# attinier85-light-sensor-shield-mk-2_0.net
KiCad netlist of a schematic drawn in EAGLE
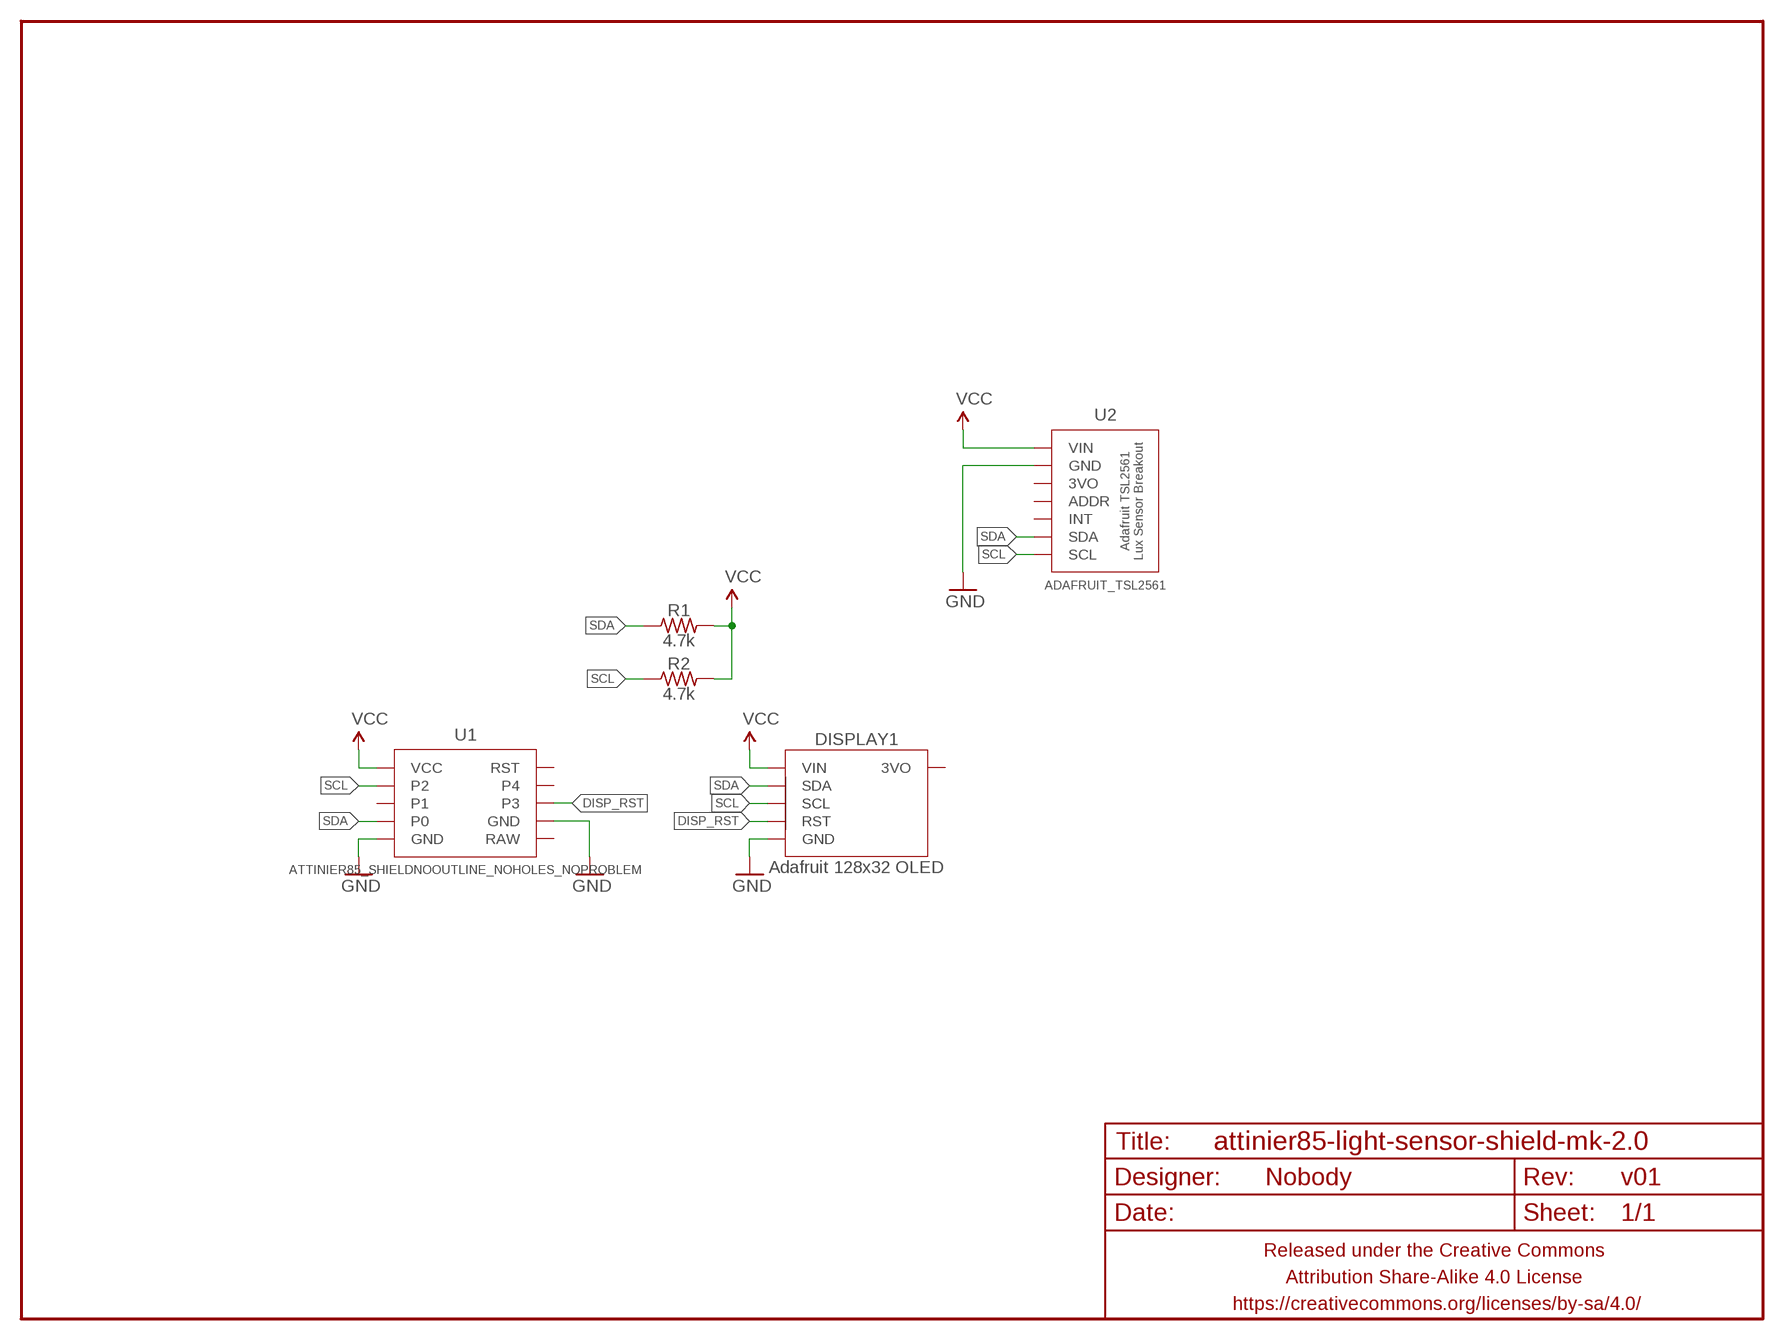
[diagram p0: schematic, sheet 1]

(export (version "E")
  (design (tool "Eeschema 10.0.6"))
  (components
    (comp (ref "DISPLAY1")
      (value "Adafruit 128x32 OLED")
      (footprint "eagle-import:ADAFRUIT_128X32_OLED_I2C_CLOSER_NOTITLE")
      (libsource (lib "eagle-import") (part "ADAFRUIT_128X32_OLED_I2CNOTITLE"))
    )
    (comp (ref "FRAME1")
      (value "FRAME-LETTERNO_PACKAGE")
      (footprint "eagle-import:DUMMY")
      (fields (field (name "DESIGNER") "Nobody"))
      (libsource (lib "eagle-import") (part "FRAME-LETTERNO_PACKAGE"))
    )
    (comp (ref "R1")
      (value "4.7k")
      (footprint "eagle-import:RESISTOR-AXIAL-PTH-7.62MM")
      (libsource (lib "eagle-import") (part "RESISTORPTH-AXIAL-7.62MM"))
    )
    (comp (ref "R2")
      (value "4.7k")
      (footprint "eagle-import:RESISTOR-AXIAL-PTH-7.62MM")
      (libsource (lib "eagle-import") (part "RESISTORPTH-AXIAL-7.62MM"))
    )
    (comp (ref "U1")
      (value "ATTINIER85_SHIELDNOOUTLINE_NOHOLES_NOPROBLEM")
      (footprint "eagle-import:ATTINIER_SHIELD_NOOUTLINE_NOHOLES")
      (libsource (lib "eagle-import") (part "ATTINIER85_SHIELDNOOUTLINE_NOHOLES_NOPROBLEM"))
    )
    (comp (ref "U2")
      (value "ADAFRUIT_TSL2561")
      (footprint "eagle-import:ADAFRUIT_TSL2561")
      (libsource (lib "eagle-import") (part "ADAFRUIT_TSL2561"))
    )
  )
  (nets
    (net (code "1") (name "DISP_RST") (class "Default")
      (node (ref "DISPLAY1") (pin "RST") (pinfunction "RST_RST") (pintype "bidirectional"))
      (node (ref "U1") (pin "3") (pinfunction "P3_3") (pintype "bidirectional"))
    )
    (net (code "2") (name "GND") (class "Default")
      (node (ref "DISPLAY1") (pin "GND") (pinfunction "GND_GND") (pintype "bidirectional"))
      (node (ref "U1") (pin "GND@1") (pinfunction "GND_GND@1") (pintype "bidirectional"))
      (node (ref "U1") (pin "GND@2") (pinfunction "GND_GND@2") (pintype "bidirectional"))
      (node (ref "U2") (pin "GND") (pinfunction "GND_GND") (pintype "bidirectional"))
    )
    (net (code "3") (name "SCL") (class "Default")
      (node (ref "DISPLAY1") (pin "SCL") (pinfunction "SCL_SCL") (pintype "bidirectional"))
      (node (ref "R2") (pin "P$1") (pinfunction "1_P$1") (pintype "passive"))
      (node (ref "U1") (pin "2") (pinfunction "P2_2") (pintype "bidirectional"))
      (node (ref "U2") (pin "SCL") (pinfunction "SCL_SCL") (pintype "bidirectional"))
    )
    (net (code "4") (name "SDA") (class "Default")
      (node (ref "DISPLAY1") (pin "SDA") (pinfunction "SDA_SDA") (pintype "bidirectional"))
      (node (ref "R1") (pin "P$1") (pinfunction "1_P$1") (pintype "passive"))
      (node (ref "U1") (pin "0") (pinfunction "P0_0") (pintype "bidirectional"))
      (node (ref "U2") (pin "SDA") (pinfunction "SDA_SDA") (pintype "bidirectional"))
    )
    (net (code "5") (name "VCC") (class "Default")
      (node (ref "DISPLAY1") (pin "VIN") (pinfunction "VIN_VIN") (pintype "bidirectional"))
      (node (ref "R1") (pin "P$2") (pinfunction "2_P$2") (pintype "passive"))
      (node (ref "R2") (pin "P$2") (pinfunction "2_P$2") (pintype "passive"))
      (node (ref "U1") (pin "VCC") (pinfunction "VCC_VCC") (pintype "bidirectional"))
      (node (ref "U2") (pin "VIN") (pinfunction "VIN_VIN") (pintype "bidirectional"))
    )
    (net (code "6") (name "unconnected-(DISPLAY1-Pad3VO)") (class "Default")
      (node (ref "DISPLAY1") (pin "3VO") (pinfunction "3VO_3VO") (pintype "bidirectional"))
    )
    (net (code "7") (name "unconnected-(U1-P1-Pad1)") (class "Default")
      (node (ref "U1") (pin "1") (pinfunction "P1_1") (pintype "bidirectional"))
    )
    (net (code "8") (name "unconnected-(U1-P4-Pad4)") (class "Default")
      (node (ref "U1") (pin "4") (pinfunction "P4_4") (pintype "bidirectional"))
    )
    (net (code "9") (name "unconnected-(U1-PadRAW)") (class "Default")
      (node (ref "U1") (pin "RAW") (pinfunction "RAW_RAW") (pintype "bidirectional"))
    )
    (net (code "10") (name "unconnected-(U1-PadRST)") (class "Default")
      (node (ref "U1") (pin "RST") (pinfunction "RST_RST") (pintype "bidirectional"))
    )
    (net (code "11") (name "unconnected-(U2-Pad3VO)") (class "Default")
      (node (ref "U2") (pin "3VO") (pinfunction "3VO_3VO") (pintype "bidirectional"))
    )
    (net (code "12") (name "unconnected-(U2-PadADDR)") (class "Default")
      (node (ref "U2") (pin "ADDR") (pinfunction "ADDR_ADDR") (pintype "bidirectional"))
    )
    (net (code "13") (name "unconnected-(U2-PadINT)") (class "Default")
      (node (ref "U2") (pin "INT") (pinfunction "INT_INT") (pintype "bidirectional"))
    )
  )
)
